# design.net
KiCad netlist of a schematic drawn in Altium Designer
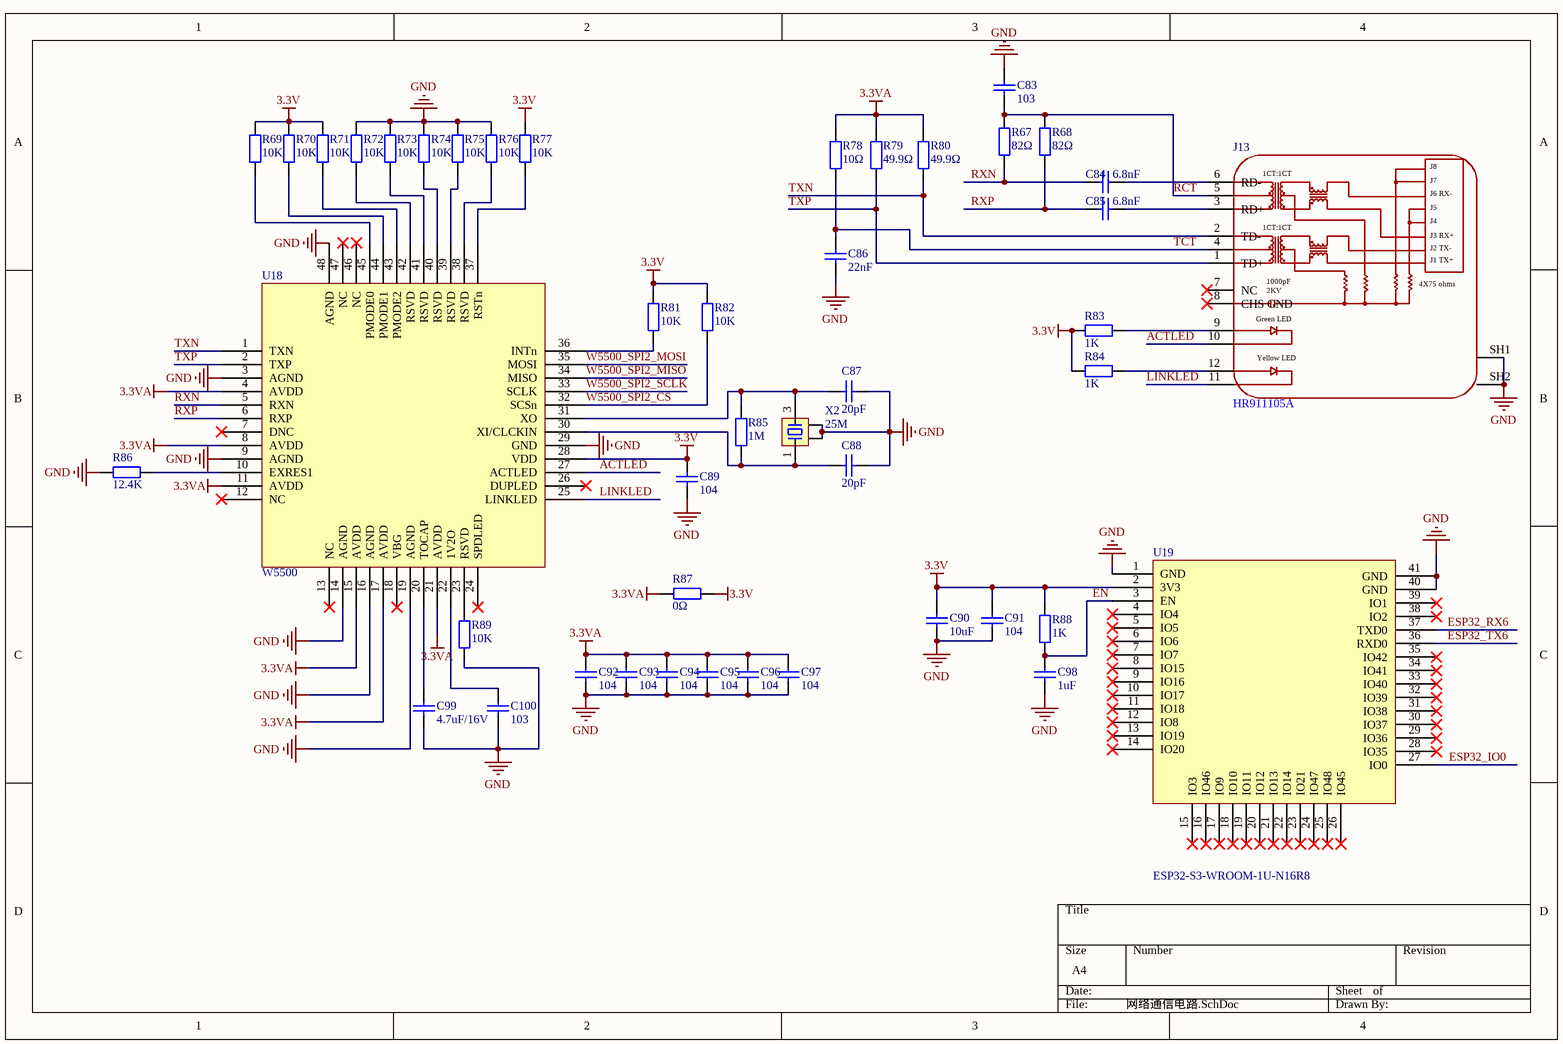
[diagram p0: 网络通信电路.SchDoc]

(export (version "E")
  (design (tool "Eeschema 10.0.6"))
  (components
    (comp (ref "C83")
      (value "103")
      (footprint "C 0603_L")
      (description "0603贴片电容")
      (fields (field (name "PUBLISHER") "Altium Limited"))
      (libsource (lib "STM32_PLC_20251215") (part "Cap"))
    )
    (comp (ref "C84")
      (value "6.8nF")
      (footprint "C 0603_L")
      (description "0603贴片电容")
      (fields (field (name "PUBLISHER") "Altium Limited"))
      (libsource (lib "STM32_PLC_20251215") (part "Cap"))
    )
    (comp (ref "C85")
      (value "6.8nF")
      (footprint "C 0603_L")
      (description "0603贴片电容")
      (fields (field (name "PUBLISHER") "Altium Limited"))
      (libsource (lib "STM32_PLC_20251215") (part "Cap"))
    )
    (comp (ref "C86")
      (value "22nF")
      (footprint "C 0603_L")
      (description "0603贴片电容")
      (fields (field (name "PUBLISHER") "Altium Limited"))
      (libsource (lib "STM32_PLC_20251215") (part "Cap"))
    )
    (comp (ref "C87")
      (value "20pF")
      (footprint "C 0603_L")
      (description "0603贴片电容")
      (fields (field (name "PUBLISHER") "Altium Limited"))
      (libsource (lib "STM32_PLC_20251215") (part "Cap"))
    )
    (comp (ref "C88")
      (value "20pF")
      (footprint "C 0603_L")
      (description "0603贴片电容")
      (fields (field (name "PUBLISHER") "Altium Limited"))
      (libsource (lib "STM32_PLC_20251215") (part "Cap"))
    )
    (comp (ref "C89")
      (value "104")
      (footprint "C 0603_L")
      (description "0603贴片电容")
      (fields (field (name "PUBLISHER") "Altium Limited"))
      (libsource (lib "STM32_PLC_20251215") (part "Cap"))
    )
    (comp (ref "C90")
      (value "10uF")
      (footprint "C 0603_L")
      (description "0603贴片电容")
      (fields (field (name "PUBLISHER") "Altium Limited"))
      (libsource (lib "STM32_PLC_20251215") (part "Cap"))
    )
    (comp (ref "C91")
      (value "104")
      (footprint "C 0603_L")
      (description "0603贴片电容")
      (fields (field (name "PUBLISHER") "Altium Limited"))
      (libsource (lib "STM32_PLC_20251215") (part "Cap"))
    )
    (comp (ref "C92")
      (value "104")
      (footprint "C 0603_L")
      (description "0603贴片电容")
      (fields (field (name "PUBLISHER") "Altium Limited"))
      (libsource (lib "STM32_PLC_20251215") (part "Cap"))
    )
    (comp (ref "C93")
      (value "104")
      (footprint "C 0603_L")
      (description "0603贴片电容")
      (fields (field (name "PUBLISHER") "Altium Limited"))
      (libsource (lib "STM32_PLC_20251215") (part "Cap"))
    )
    (comp (ref "C94")
      (value "104")
      (footprint "C 0603_L")
      (description "0603贴片电容")
      (fields (field (name "PUBLISHER") "Altium Limited"))
      (libsource (lib "STM32_PLC_20251215") (part "Cap"))
    )
    (comp (ref "C95")
      (value "104")
      (footprint "C 0603_L")
      (description "0603贴片电容")
      (fields (field (name "PUBLISHER") "Altium Limited"))
      (libsource (lib "STM32_PLC_20251215") (part "Cap"))
    )
    (comp (ref "C96")
      (value "104")
      (footprint "C 0603_L")
      (description "0603贴片电容")
      (fields (field (name "PUBLISHER") "Altium Limited"))
      (libsource (lib "STM32_PLC_20251215") (part "Cap"))
    )
    (comp (ref "C97")
      (value "104")
      (footprint "C 0603_L")
      (description "0603贴片电容")
      (fields (field (name "PUBLISHER") "Altium Limited"))
      (libsource (lib "STM32_PLC_20251215") (part "Cap"))
    )
    (comp (ref "C98")
      (value "1uF")
      (footprint "C 0603_L")
      (description "0603贴片电容")
      (fields (field (name "PUBLISHER") "Altium Limited"))
      (libsource (lib "STM32_PLC_20251215") (part "Cap"))
    )
    (comp (ref "C99")
      (value "4.7uF/16V")
      (footprint "C 0603_L")
      (description "0603贴片电容")
      (fields (field (name "PUBLISHER") "Altium Limited"))
      (libsource (lib "STM32_PLC_20251215") (part "Cap"))
    )
    (comp (ref "C100")
      (value "103")
      (footprint "C 0603_L")
      (description "0603贴片电容")
      (fields (field (name "PUBLISHER") "Altium Limited"))
      (libsource (lib "STM32_PLC_20251215") (part "Cap"))
    )
    (comp (ref "J13")
      (value "HR911105A")
      (footprint "RJ45-TH_HR911105A")
      (description "网口")
      (fields (field (name "MANUFACTURER") "HANRUN(汉仁)"))
      (libsource (lib "STM32_PLC_20251215") (part "HR911105A_C12074"))
    )
    (comp (ref "R67")
      (value "82Ω")
      (footprint "R 0603_L")
      (description "C0603贴片电阻")
      (fields (field (name "版权归属") "源创客"))
      (libsource (lib "STM32_PLC_20251215") (part "Res"))
    )
    (comp (ref "R68")
      (value "82Ω")
      (footprint "R 0603_L")
      (description "C0603贴片电阻")
      (fields (field (name "版权归属") "源创客"))
      (libsource (lib "STM32_PLC_20251215") (part "Res"))
    )
    (comp (ref "R69")
      (value "10K")
      (footprint "R 0603_L")
      (description "C0603贴片电阻")
      (fields (field (name "版权归属") "源创客"))
      (libsource (lib "STM32_PLC_20251215") (part "Res"))
    )
    (comp (ref "R70")
      (value "10K")
      (footprint "R 0603_L")
      (description "C0603贴片电阻")
      (fields (field (name "版权归属") "源创客"))
      (libsource (lib "STM32_PLC_20251215") (part "Res"))
    )
    (comp (ref "R71")
      (value "10K")
      (footprint "R 0603_L")
      (description "C0603贴片电阻")
      (fields (field (name "版权归属") "源创客"))
      (libsource (lib "STM32_PLC_20251215") (part "Res"))
    )
    (comp (ref "R72")
      (value "10K")
      (footprint "R 0603_L")
      (description "C0603贴片电阻")
      (fields (field (name "版权归属") "源创客"))
      (libsource (lib "STM32_PLC_20251215") (part "Res"))
    )
    (comp (ref "R73")
      (value "10K")
      (footprint "R 0603_L")
      (description "C0603贴片电阻")
      (fields (field (name "版权归属") "源创客"))
      (libsource (lib "STM32_PLC_20251215") (part "Res"))
    )
    (comp (ref "R74")
      (value "10K")
      (footprint "R 0603_L")
      (description "C0603贴片电阻")
      (fields (field (name "版权归属") "源创客"))
      (libsource (lib "STM32_PLC_20251215") (part "Res"))
    )
    (comp (ref "R75")
      (value "10K")
      (footprint "R 0603_L")
      (description "C0603贴片电阻")
      (fields (field (name "版权归属") "源创客"))
      (libsource (lib "STM32_PLC_20251215") (part "Res"))
    )
    (comp (ref "R76")
      (value "10K")
      (footprint "R 0603_L")
      (description "C0603贴片电阻")
      (fields (field (name "版权归属") "源创客"))
      (libsource (lib "STM32_PLC_20251215") (part "Res"))
    )
    (comp (ref "R77")
      (value "10K")
      (footprint "R 0603_L")
      (description "C0603贴片电阻")
      (fields (field (name "版权归属") "源创客"))
      (libsource (lib "STM32_PLC_20251215") (part "Res"))
    )
    (comp (ref "R78")
      (value "10Ω")
      (footprint "R 0603_L")
      (description "C0603贴片电阻")
      (fields (field (name "版权归属") "源创客"))
      (libsource (lib "STM32_PLC_20251215") (part "Res"))
    )
    (comp (ref "R79")
      (value "49.9Ω")
      (footprint "R 0603_L")
      (description "C0603贴片电阻")
      (fields (field (name "版权归属") "源创客"))
      (libsource (lib "STM32_PLC_20251215") (part "Res"))
    )
    (comp (ref "R80")
      (value "49.9Ω")
      (footprint "R 0603_L")
      (description "C0603贴片电阻")
      (fields (field (name "版权归属") "源创客"))
      (libsource (lib "STM32_PLC_20251215") (part "Res"))
    )
    (comp (ref "R81")
      (value "10K")
      (footprint "R 0603_L")
      (description "C0603贴片电阻")
      (fields (field (name "版权归属") "源创客"))
      (libsource (lib "STM32_PLC_20251215") (part "Res"))
    )
    (comp (ref "R82")
      (value "10K")
      (footprint "R 0603_L")
      (description "C0603贴片电阻")
      (fields (field (name "版权归属") "源创客"))
      (libsource (lib "STM32_PLC_20251215") (part "Res"))
    )
    (comp (ref "R83")
      (value "1K")
      (footprint "R 0603_L")
      (description "C0603贴片电阻")
      (fields (field (name "版权归属") "源创客"))
      (libsource (lib "STM32_PLC_20251215") (part "Res"))
    )
    (comp (ref "R84")
      (value "1K")
      (footprint "R 0603_L")
      (description "C0603贴片电阻")
      (fields (field (name "版权归属") "源创客"))
      (libsource (lib "STM32_PLC_20251215") (part "Res"))
    )
    (comp (ref "R85")
      (value "1M")
      (footprint "R 0603_L")
      (description "C0603贴片电阻")
      (fields (field (name "版权归属") "源创客"))
      (libsource (lib "STM32_PLC_20251215") (part "Res"))
    )
    (comp (ref "R86")
      (value "12.4K")
      (footprint "R 0603_L")
      (description "C0603贴片电阻")
      (fields (field (name "版权归属") "源创客"))
      (libsource (lib "STM32_PLC_20251215") (part "Res"))
    )
    (comp (ref "R87")
      (value "0Ω")
      (footprint "R 0603_L")
      (description "C0603贴片电阻")
      (fields (field (name "版权归属") "源创客"))
      (libsource (lib "STM32_PLC_20251215") (part "Res"))
    )
    (comp (ref "R88")
      (value "1K")
      (footprint "R 0603_L")
      (description "C0603贴片电阻")
      (fields (field (name "版权归属") "源创客"))
      (libsource (lib "STM32_PLC_20251215") (part "Res"))
    )
    (comp (ref "R89")
      (value "10K")
      (footprint "R 0603_L")
      (description "C0603贴片电阻")
      (fields (field (name "版权归属") "源创客"))
      (libsource (lib "STM32_PLC_20251215") (part "Res"))
    )
    (comp (ref "U18")
      (value "W5500")
      (footprint "LQFP48 7X7_L")
      (description "W5500以太网芯片")
      (libsource (lib "STM32_PLC_20251215") (part "W5500"))
    )
    (comp (ref "U19")
      (value "ESP32-S3-WROOM-1U-N16R8")
      (footprint "WIRELM-SMD_ESP32-S3-WROOM-1U")
      (fields (field (name "MANUFACTURER") "ESPRESSIF(乐鑫)"))
      (libsource (lib "STM32F407_PLC_20260104_") (part "ESP32-S3-WROOM-1U-N16R8"))
    )
    (comp (ref "X2")
      (value "25M")
      (footprint "OSC 3225-4P")
      (description "4脚无源晶振")
      (fields (field (name "版权归属") "封装库来自淘宝卖家 ID：黄晶宝石"))
      (libsource (lib "STM32_PLC_20251215") (part "XTAL-4P"))
    )
  )
  (nets
    (net (code "1") (name "/ACTLED") (class "Default")
      (node (ref "J13") (pin "10") (pinfunction "10_10") (pintype "passive"))
      (node (ref "U18") (pin "27") (pinfunction "ACTLED_27") (pintype "passive"))
    )
    (net (code "2") (name "/EN") (class "Default")
      (node (ref "C98") (pin "2") (pinfunction "2_2") (pintype "passive"))
      (node (ref "R88") (pin "2") (pinfunction "2_2") (pintype "passive"))
      (node (ref "U19") (pin "3") (pinfunction "EN_3") (pintype "passive"))
    )
    (net (code "3") (name "/ESP32_IO0") (class "Default")
      (node (ref "U19") (pin "27") (pinfunction "IO0_27") (pintype "passive"))
    )
    (net (code "4") (name "/ESP32_RX6") (class "Default")
      (node (ref "U19") (pin "37") (pinfunction "TXD0_37") (pintype "passive"))
    )
    (net (code "5") (name "/ESP32_TX6") (class "Default")
      (node (ref "U19") (pin "36") (pinfunction "RXD0_36") (pintype "passive"))
    )
    (net (code "6") (name "/LINKLED") (class "Default")
      (node (ref "J13") (pin "11") (pinfunction "11_11") (pintype "passive"))
      (node (ref "U18") (pin "25") (pinfunction "LINKLED_25") (pintype "passive"))
    )
    (net (code "7") (name "/RCT") (class "Default")
      (node (ref "C83") (pin "1") (pinfunction "1_1") (pintype "passive"))
      (node (ref "J13") (pin "5") (pinfunction "5_5") (pintype "passive"))
      (node (ref "R67") (pin "1") (pinfunction "1_1") (pintype "passive"))
      (node (ref "R68") (pin "1") (pinfunction "1_1") (pintype "passive"))
    )
    (net (code "8") (name "/RXN") (class "Default")
      (node (ref "C84") (pin "1") (pinfunction "1_1") (pintype "passive"))
      (node (ref "R67") (pin "2") (pinfunction "2_2") (pintype "passive"))
      (node (ref "U18") (pin "5") (pinfunction "RXN_5") (pintype "passive"))
    )
    (net (code "9") (name "/RXP") (class "Default")
      (node (ref "C85") (pin "1") (pinfunction "1_1") (pintype "passive"))
      (node (ref "R68") (pin "2") (pinfunction "2_2") (pintype "passive"))
      (node (ref "U18") (pin "6") (pinfunction "RXP_6") (pintype "passive"))
    )
    (net (code "10") (name "/TCT") (class "Default")
      (node (ref "C86") (pin "1") (pinfunction "1_1") (pintype "passive"))
      (node (ref "J13") (pin "4") (pinfunction "4_4") (pintype "passive"))
      (node (ref "R78") (pin "2") (pinfunction "2_2") (pintype "passive"))
    )
    (net (code "11") (name "/TXN") (class "Default")
      (node (ref "J13") (pin "2") (pinfunction "TD-_2") (pintype "passive"))
      (node (ref "R80") (pin "2") (pinfunction "2_2") (pintype "passive"))
      (node (ref "U18") (pin "1") (pinfunction "TXN_1") (pintype "passive"))
    )
    (net (code "12") (name "/TXP") (class "Default")
      (node (ref "J13") (pin "1") (pinfunction "TD+_1") (pintype "passive"))
      (node (ref "R79") (pin "2") (pinfunction "2_2") (pintype "passive"))
      (node (ref "U18") (pin "2") (pinfunction "TXP_2") (pintype "passive"))
    )
    (net (code "13") (name "/W5500_SPI2_CS") (class "Default")
      (node (ref "R82") (pin "1") (pinfunction "1_1") (pintype "passive"))
      (node (ref "U18") (pin "32") (pinfunction "SCSn_32") (pintype "passive"))
    )
    (net (code "14") (name "/W5500_SPI2_MISO") (class "Default")
      (node (ref "U18") (pin "34") (pinfunction "MISO_34") (pintype "passive"))
    )
    (net (code "15") (name "/W5500_SPI2_MOSI") (class "Default")
      (node (ref "U18") (pin "35") (pinfunction "MOSI_35") (pintype "passive"))
    )
    (net (code "16") (name "/W5500_SPI2_SCLK") (class "Default")
      (node (ref "U18") (pin "33") (pinfunction "SCLK_33") (pintype "passive"))
    )
    (net (code "17") (name "3.3V") (class "Default")
      (node (ref "C89") (pin "2") (pinfunction "2_2") (pintype "passive"))
      (node (ref "C90") (pin "2") (pinfunction "2_2") (pintype "passive"))
      (node (ref "C91") (pin "2") (pinfunction "2_2") (pintype "passive"))
      (node (ref "R69") (pin "2") (pinfunction "2_2") (pintype "passive"))
      (node (ref "R70") (pin "2") (pinfunction "2_2") (pintype "passive"))
      (node (ref "R71") (pin "2") (pinfunction "2_2") (pintype "passive"))
      (node (ref "R77") (pin "2") (pinfunction "2_2") (pintype "passive"))
      (node (ref "R81") (pin "2") (pinfunction "2_2") (pintype "passive"))
      (node (ref "R82") (pin "2") (pinfunction "2_2") (pintype "passive"))
      (node (ref "R83") (pin "2") (pinfunction "2_2") (pintype "passive"))
      (node (ref "R84") (pin "2") (pinfunction "2_2") (pintype "passive"))
      (node (ref "R87") (pin "2") (pinfunction "2_2") (pintype "passive"))
      (node (ref "R88") (pin "1") (pinfunction "1_1") (pintype "passive"))
      (node (ref "U18") (pin "28") (pinfunction "VDD_28") (pintype "passive"))
      (node (ref "U19") (pin "2") (pinfunction "3V3_2") (pintype "passive"))
    )
    (net (code "18") (name "3.3VA") (class "Default")
      (node (ref "C92") (pin "2") (pinfunction "2_2") (pintype "passive"))
      (node (ref "C93") (pin "2") (pinfunction "2_2") (pintype "passive"))
      (node (ref "C94") (pin "2") (pinfunction "2_2") (pintype "passive"))
      (node (ref "C95") (pin "2") (pinfunction "2_2") (pintype "passive"))
      (node (ref "C96") (pin "2") (pinfunction "2_2") (pintype "passive"))
      (node (ref "C97") (pin "2") (pinfunction "2_2") (pintype "passive"))
      (node (ref "R78") (pin "1") (pinfunction "1_1") (pintype "passive"))
      (node (ref "R79") (pin "1") (pinfunction "1_1") (pintype "passive"))
      (node (ref "R80") (pin "1") (pinfunction "1_1") (pintype "passive"))
      (node (ref "R87") (pin "1") (pinfunction "1_1") (pintype "passive"))
      (node (ref "U18") (pin "11") (pinfunction "AVDD_11") (pintype "passive"))
      (node (ref "U18") (pin "15") (pinfunction "AVDD_15") (pintype "passive"))
      (node (ref "U18") (pin "17") (pinfunction "AVDD_17") (pintype "passive"))
      (node (ref "U18") (pin "21") (pinfunction "AVDD_21") (pintype "passive"))
      (node (ref "U18") (pin "4") (pinfunction "AVDD_4") (pintype "passive"))
      (node (ref "U18") (pin "8") (pinfunction "AVDD_8") (pintype "passive"))
    )
    (net (code "19") (name "GND") (class "Default")
      (node (ref "C100") (pin "1") (pinfunction "1_1") (pintype "passive"))
      (node (ref "C83") (pin "2") (pinfunction "2_2") (pintype "passive"))
      (node (ref "C86") (pin "2") (pinfunction "2_2") (pintype "passive"))
      (node (ref "C87") (pin "1") (pinfunction "1_1") (pintype "passive"))
      (node (ref "C88") (pin "1") (pinfunction "1_1") (pintype "passive"))
      (node (ref "C89") (pin "1") (pinfunction "1_1") (pintype "passive"))
      (node (ref "C90") (pin "1") (pinfunction "1_1") (pintype "passive"))
      (node (ref "C91") (pin "1") (pinfunction "1_1") (pintype "passive"))
      (node (ref "C92") (pin "1") (pinfunction "1_1") (pintype "passive"))
      (node (ref "C93") (pin "1") (pinfunction "1_1") (pintype "passive"))
      (node (ref "C94") (pin "1") (pinfunction "1_1") (pintype "passive"))
      (node (ref "C95") (pin "1") (pinfunction "1_1") (pintype "passive"))
      (node (ref "C96") (pin "1") (pinfunction "1_1") (pintype "passive"))
      (node (ref "C97") (pin "1") (pinfunction "1_1") (pintype "passive"))
      (node (ref "C98") (pin "1") (pinfunction "1_1") (pintype "passive"))
      (node (ref "C99") (pin "1") (pinfunction "1_1") (pintype "passive"))
      (node (ref "J13") (pin "SH1") (pinfunction "SH1_SH1") (pintype "passive"))
      (node (ref "J13") (pin "SH2") (pinfunction "SH2_SH2") (pintype "passive"))
      (node (ref "R72") (pin "2") (pinfunction "2_2") (pintype "passive"))
      (node (ref "R73") (pin "2") (pinfunction "2_2") (pintype "passive"))
      (node (ref "R74") (pin "2") (pinfunction "2_2") (pintype "passive"))
      (node (ref "R75") (pin "2") (pinfunction "2_2") (pintype "passive"))
      (node (ref "R76") (pin "2") (pinfunction "2_2") (pintype "passive"))
      (node (ref "R86") (pin "1") (pinfunction "1_1") (pintype "passive"))
      (node (ref "R89") (pin "1") (pinfunction "1_1") (pintype "passive"))
      (node (ref "U18") (pin "14") (pinfunction "AGND_14") (pintype "passive"))
      (node (ref "U18") (pin "16") (pinfunction "AGND_16") (pintype "passive"))
      (node (ref "U18") (pin "19") (pinfunction "AGND_19") (pintype "passive"))
      (node (ref "U18") (pin "29") (pinfunction "GND_29") (pintype "passive"))
      (node (ref "U18") (pin "3") (pinfunction "AGND_3") (pintype "passive"))
      (node (ref "U18") (pin "48") (pinfunction "AGND_48") (pintype "passive"))
      (node (ref "U18") (pin "9") (pinfunction "AGND_9") (pintype "passive"))
      (node (ref "U19") (pin "1") (pinfunction "GND_1") (pintype "passive"))
      (node (ref "U19") (pin "40") (pinfunction "GND_40") (pintype "passive"))
      (node (ref "U19") (pin "41") (pinfunction "GND_41") (pintype "passive"))
      (node (ref "X2") (pin "2") (pinfunction "2_2") (pintype "passive"))
      (node (ref "X2") (pin "4") (pinfunction "4_4") (pintype "passive"))
    )
    (net (code "20") (name "Net-(J13-Pad9)") (class "Default")
      (node (ref "J13") (pin "9") (pinfunction "9_9") (pintype "passive"))
      (node (ref "R83") (pin "1") (pinfunction "1_1") (pintype "passive"))
    )
    (net (code "21") (name "Net-(J13-Pad12)") (class "Default")
      (node (ref "J13") (pin "12") (pinfunction "12_12") (pintype "passive"))
      (node (ref "R84") (pin "1") (pinfunction "1_1") (pintype "passive"))
    )
    (net (code "22") (name "Net-(J13-RD+)") (class "Default")
      (node (ref "C85") (pin "2") (pinfunction "2_2") (pintype "passive"))
      (node (ref "J13") (pin "3") (pinfunction "RD+_3") (pintype "passive"))
    )
    (net (code "23") (name "Net-(J13-RD-)") (class "Default")
      (node (ref "C84") (pin "2") (pinfunction "2_2") (pintype "passive"))
      (node (ref "J13") (pin "6") (pinfunction "RD-_6") (pintype "passive"))
    )
    (net (code "24") (name "Net-(R72-Pad1)") (class "Default")
      (node (ref "R72") (pin "1") (pinfunction "1_1") (pintype "passive"))
      (node (ref "U18") (pin "42") (pinfunction "RSVD_42") (pintype "passive"))
    )
    (net (code "25") (name "Net-(R73-Pad1)") (class "Default")
      (node (ref "R73") (pin "1") (pinfunction "1_1") (pintype "passive"))
      (node (ref "U18") (pin "41") (pinfunction "RSVD_41") (pintype "passive"))
    )
    (net (code "26") (name "Net-(R74-Pad1)") (class "Default")
      (node (ref "R74") (pin "1") (pinfunction "1_1") (pintype "passive"))
      (node (ref "U18") (pin "40") (pinfunction "RSVD_40") (pintype "passive"))
    )
    (net (code "27") (name "Net-(R75-Pad1)") (class "Default")
      (node (ref "R75") (pin "1") (pinfunction "1_1") (pintype "passive"))
      (node (ref "U18") (pin "39") (pinfunction "RSVD_39") (pintype "passive"))
    )
    (net (code "28") (name "Net-(R76-Pad1)") (class "Default")
      (node (ref "R76") (pin "1") (pinfunction "1_1") (pintype "passive"))
      (node (ref "U18") (pin "38") (pinfunction "RSVD_38") (pintype "passive"))
    )
    (net (code "29") (name "Net-(R89-Pad2)") (class "Default")
      (node (ref "R89") (pin "2") (pinfunction "2_2") (pintype "passive"))
      (node (ref "U18") (pin "23") (pinfunction "RSVD_23") (pintype "passive"))
    )
    (net (code "30") (name "Net-(U18-1V2O)") (class "Default")
      (node (ref "C100") (pin "2") (pinfunction "2_2") (pintype "passive"))
      (node (ref "U18") (pin "22") (pinfunction "1V2O_22") (pintype "passive"))
    )
    (net (code "31") (name "Net-(U18-EXRES1)") (class "Default")
      (node (ref "R86") (pin "2") (pinfunction "2_2") (pintype "passive"))
      (node (ref "U18") (pin "10") (pinfunction "EXRES1_10") (pintype "passive"))
    )
    (net (code "32") (name "Net-(U18-INTn)") (class "Default")
      (node (ref "R81") (pin "1") (pinfunction "1_1") (pintype "passive"))
      (node (ref "U18") (pin "36") (pinfunction "INTn_36") (pintype "passive"))
    )
    (net (code "33") (name "Net-(U18-PMODE0)") (class "Default")
      (node (ref "R69") (pin "1") (pinfunction "1_1") (pintype "passive"))
      (node (ref "U18") (pin "45") (pinfunction "PMODE0_45") (pintype "passive"))
    )
    (net (code "34") (name "Net-(U18-PMODE1)") (class "Default")
      (node (ref "R70") (pin "1") (pinfunction "1_1") (pintype "passive"))
      (node (ref "U18") (pin "44") (pinfunction "PMODE1_44") (pintype "passive"))
    )
    (net (code "35") (name "Net-(U18-PMODE2)") (class "Default")
      (node (ref "R71") (pin "1") (pinfunction "1_1") (pintype "passive"))
      (node (ref "U18") (pin "43") (pinfunction "PMODE2_43") (pintype "passive"))
    )
    (net (code "36") (name "Net-(U18-RSTn)") (class "Default")
      (node (ref "R77") (pin "1") (pinfunction "1_1") (pintype "passive"))
      (node (ref "U18") (pin "37") (pinfunction "RSTn_37") (pintype "passive"))
    )
    (net (code "37") (name "Net-(U18-TOCAP)") (class "Default")
      (node (ref "C99") (pin "2") (pinfunction "2_2") (pintype "passive"))
      (node (ref "U18") (pin "20") (pinfunction "TOCAP_20") (pintype "passive"))
    )
    (net (code "38") (name "Net-(U18-XI{slash}CLCKIN)") (class "Default")
      (node (ref "C88") (pin "2") (pinfunction "2_2") (pintype "passive"))
      (node (ref "R85") (pin "1") (pinfunction "1_1") (pintype "passive"))
      (node (ref "U18") (pin "30") (pinfunction "XI/CLCKIN_30") (pintype "passive"))
      (node (ref "X2") (pin "1") (pinfunction "1_1") (pintype "passive"))
    )
    (net (code "39") (name "Net-(U18-XO)") (class "Default")
      (node (ref "C87") (pin "2") (pinfunction "2_2") (pintype "passive"))
      (node (ref "R85") (pin "2") (pinfunction "2_2") (pintype "passive"))
      (node (ref "U18") (pin "31") (pinfunction "XO_31") (pintype "passive"))
      (node (ref "X2") (pin "3") (pinfunction "3_3") (pintype "passive"))
    )
    (net (code "40") (name "unconnected-(J13-CHS_GND-Pad8)") (class "Default")
      (node (ref "J13") (pin "8") (pinfunction "CHS_GND_8") (pintype "passive+no_connect"))
    )
    (net (code "41") (name "unconnected-(J13-NC-Pad7)") (class "Default")
      (node (ref "J13") (pin "7") (pinfunction "NC_7") (pintype "passive+no_connect"))
    )
    (net (code "42") (name "unconnected-(U18-DNC-Pad7)") (class "Default")
      (node (ref "U18") (pin "7") (pinfunction "DNC_7") (pintype "passive+no_connect"))
    )
    (net (code "43") (name "unconnected-(U18-DUPLED-Pad26)") (class "Default")
      (node (ref "U18") (pin "26") (pinfunction "DUPLED_26") (pintype "passive+no_connect"))
    )
    (net (code "44") (name "unconnected-(U18-NC-Pad12)") (class "Default")
      (node (ref "U18") (pin "12") (pinfunction "NC_12") (pintype "passive+no_connect"))
    )
    (net (code "45") (name "unconnected-(U18-NC-Pad13)") (class "Default")
      (node (ref "U18") (pin "13") (pinfunction "NC_13") (pintype "passive+no_connect"))
    )
    (net (code "46") (name "unconnected-(U18-NC-Pad46)") (class "Default")
      (node (ref "U18") (pin "46") (pinfunction "NC_46") (pintype "passive+no_connect"))
    )
    (net (code "47") (name "unconnected-(U18-NC-Pad47)") (class "Default")
      (node (ref "U18") (pin "47") (pinfunction "NC_47") (pintype "passive+no_connect"))
    )
    (net (code "48") (name "unconnected-(U18-SPDLED-Pad24)") (class "Default")
      (node (ref "U18") (pin "24") (pinfunction "SPDLED_24") (pintype "passive+no_connect"))
    )
    (net (code "49") (name "unconnected-(U18-VBG-Pad18)") (class "Default")
      (node (ref "U18") (pin "18") (pinfunction "VBG_18") (pintype "passive+no_connect"))
    )
    (net (code "50") (name "unconnected-(U19-IO1-Pad39)") (class "Default")
      (node (ref "U19") (pin "39") (pinfunction "IO1_39") (pintype "passive+no_connect"))
    )
    (net (code "51") (name "unconnected-(U19-IO2-Pad38)") (class "Default")
      (node (ref "U19") (pin "38") (pinfunction "IO2_38") (pintype "passive+no_connect"))
    )
    (net (code "52") (name "unconnected-(U19-IO3-Pad15)") (class "Default")
      (node (ref "U19") (pin "15") (pinfunction "IO3_15") (pintype "passive+no_connect"))
    )
    (net (code "53") (name "unconnected-(U19-IO4-Pad4)") (class "Default")
      (node (ref "U19") (pin "4") (pinfunction "IO4_4") (pintype "passive+no_connect"))
    )
    (net (code "54") (name "unconnected-(U19-IO5-Pad5)") (class "Default")
      (node (ref "U19") (pin "5") (pinfunction "IO5_5") (pintype "passive+no_connect"))
    )
    (net (code "55") (name "unconnected-(U19-IO6-Pad6)") (class "Default")
      (node (ref "U19") (pin "6") (pinfunction "IO6_6") (pintype "passive+no_connect"))
    )
    (net (code "56") (name "unconnected-(U19-IO7-Pad7)") (class "Default")
      (node (ref "U19") (pin "7") (pinfunction "IO7_7") (pintype "passive+no_connect"))
    )
    (net (code "57") (name "unconnected-(U19-IO8-Pad12)") (class "Default")
      (node (ref "U19") (pin "12") (pinfunction "IO8_12") (pintype "passive+no_connect"))
    )
    (net (code "58") (name "unconnected-(U19-IO9-Pad17)") (class "Default")
      (node (ref "U19") (pin "17") (pinfunction "IO9_17") (pintype "passive+no_connect"))
    )
    (net (code "59") (name "unconnected-(U19-IO10-Pad18)") (class "Default")
      (node (ref "U19") (pin "18") (pinfunction "IO10_18") (pintype "passive+no_connect"))
    )
    (net (code "60") (name "unconnected-(U19-IO11-Pad19)") (class "Default")
      (node (ref "U19") (pin "19") (pinfunction "IO11_19") (pintype "passive+no_connect"))
    )
    (net (code "61") (name "unconnected-(U19-IO12-Pad20)") (class "Default")
      (node (ref "U19") (pin "20") (pinfunction "IO12_20") (pintype "passive+no_connect"))
    )
    (net (code "62") (name "unconnected-(U19-IO13-Pad21)") (class "Default")
      (node (ref "U19") (pin "21") (pinfunction "IO13_21") (pintype "passive+no_connect"))
    )
    (net (code "63") (name "unconnected-(U19-IO14-Pad22)") (class "Default")
      (node (ref "U19") (pin "22") (pinfunction "IO14_22") (pintype "passive+no_connect"))
    )
    (net (code "64") (name "unconnected-(U19-IO15-Pad8)") (class "Default")
      (node (ref "U19") (pin "8") (pinfunction "IO15_8") (pintype "passive+no_connect"))
    )
    (net (code "65") (name "unconnected-(U19-IO16-Pad9)") (class "Default")
      (node (ref "U19") (pin "9") (pinfunction "IO16_9") (pintype "passive+no_connect"))
    )
    (net (code "66") (name "unconnected-(U19-IO17-Pad10)") (class "Default")
      (node (ref "U19") (pin "10") (pinfunction "IO17_10") (pintype "passive+no_connect"))
    )
    (net (code "67") (name "unconnected-(U19-IO18-Pad11)") (class "Default")
      (node (ref "U19") (pin "11") (pinfunction "IO18_11") (pintype "passive+no_connect"))
    )
    (net (code "68") (name "unconnected-(U19-IO19-Pad13)") (class "Default")
      (node (ref "U19") (pin "13") (pinfunction "IO19_13") (pintype "passive+no_connect"))
    )
    (net (code "69") (name "unconnected-(U19-IO20-Pad14)") (class "Default")
      (node (ref "U19") (pin "14") (pinfunction "IO20_14") (pintype "passive+no_connect"))
    )
    (net (code "70") (name "unconnected-(U19-IO21-Pad23)") (class "Default")
      (node (ref "U19") (pin "23") (pinfunction "IO21_23") (pintype "passive+no_connect"))
    )
    (net (code "71") (name "unconnected-(U19-IO35-Pad28)") (class "Default")
      (node (ref "U19") (pin "28") (pinfunction "IO35_28") (pintype "passive+no_connect"))
    )
    (net (code "72") (name "unconnected-(U19-IO36-Pad29)") (class "Default")
      (node (ref "U19") (pin "29") (pinfunction "IO36_29") (pintype "passive+no_connect"))
    )
    (net (code "73") (name "unconnected-(U19-IO37-Pad30)") (class "Default")
      (node (ref "U19") (pin "30") (pinfunction "IO37_30") (pintype "passive+no_connect"))
    )
    (net (code "74") (name "unconnected-(U19-IO38-Pad31)") (class "Default")
      (node (ref "U19") (pin "31") (pinfunction "IO38_31") (pintype "passive+no_connect"))
    )
    (net (code "75") (name "unconnected-(U19-IO39-Pad32)") (class "Default")
      (node (ref "U19") (pin "32") (pinfunction "IO39_32") (pintype "passive+no_connect"))
    )
    (net (code "76") (name "unconnected-(U19-IO40-Pad33)") (class "Default")
      (node (ref "U19") (pin "33") (pinfunction "IO40_33") (pintype "passive+no_connect"))
    )
    (net (code "77") (name "unconnected-(U19-IO41-Pad34)") (class "Default")
      (node (ref "U19") (pin "34") (pinfunction "IO41_34") (pintype "passive+no_connect"))
    )
    (net (code "78") (name "unconnected-(U19-IO42-Pad35)") (class "Default")
      (node (ref "U19") (pin "35") (pinfunction "IO42_35") (pintype "passive+no_connect"))
    )
    (net (code "79") (name "unconnected-(U19-IO45-Pad26)") (class "Default")
      (node (ref "U19") (pin "26") (pinfunction "IO45_26") (pintype "passive+no_connect"))
    )
    (net (code "80") (name "unconnected-(U19-IO46-Pad16)") (class "Default")
      (node (ref "U19") (pin "16") (pinfunction "IO46_16") (pintype "passive+no_connect"))
    )
    (net (code "81") (name "unconnected-(U19-IO47-Pad24)") (class "Default")
      (node (ref "U19") (pin "24") (pinfunction "IO47_24") (pintype "passive+no_connect"))
    )
    (net (code "82") (name "unconnected-(U19-IO48-Pad25)") (class "Default")
      (node (ref "U19") (pin "25") (pinfunction "IO48_25") (pintype "passive+no_connect"))
    )
  )
)
